# ESP8266ServoGPIOServerAP.net
KiCad netlist of a schematic drawn in EAGLE
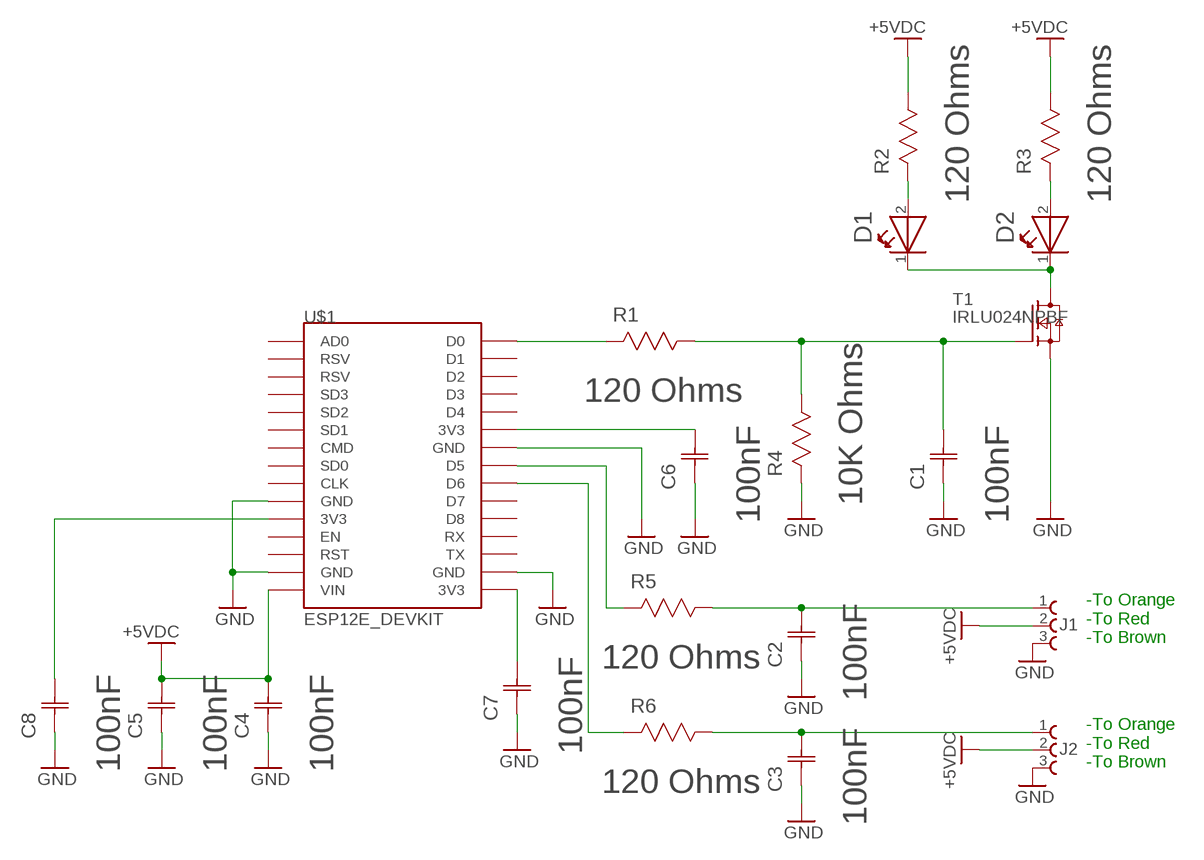
[diagram p0: schematic, sheet 1]

(export (version "E")
  (design (tool "Eeschema 10.0.6"))
  (components
    (comp (ref "C1")
      (value "100nF")
      (footprint "eagle-import:CAPC2013X135N")
      (fields (field (name "MPN") "GRM21BR60J226ME39L ") (field (name "TOLERANCE") "±20%"))
      (libsource (lib "eagle-import") (part "GRM21BR60J226ME39L"))
    )
    (comp (ref "C2")
      (value "100nF")
      (footprint "eagle-import:CAPC2013X135N")
      (fields (field (name "MPN") "GRM21BR60J226ME39L ") (field (name "TOLERANCE") "±20%"))
      (libsource (lib "eagle-import") (part "GRM21BR60J226ME39L"))
    )
    (comp (ref "C3")
      (value "100nF")
      (footprint "eagle-import:CAPC2013X135N")
      (fields (field (name "MPN") "GRM21BR60J226ME39L ") (field (name "TOLERANCE") "±20%"))
      (libsource (lib "eagle-import") (part "GRM21BR60J226ME39L"))
    )
    (comp (ref "C4")
      (value "100nF")
      (footprint "eagle-import:CAPC2013X135N")
      (fields (field (name "MPN") "GRM21BR60J226ME39L ") (field (name "TOLERANCE") "±20%"))
      (libsource (lib "eagle-import") (part "GRM21BR60J226ME39L"))
    )
    (comp (ref "C5")
      (value "100nF")
      (footprint "eagle-import:CAPC2013X135N")
      (fields (field (name "MPN") "GRM21BR60J226ME39L ") (field (name "TOLERANCE") "±20%"))
      (libsource (lib "eagle-import") (part "GRM21BR60J226ME39L"))
    )
    (comp (ref "C6")
      (value "100nF")
      (footprint "eagle-import:CAPC2013X135N")
      (fields (field (name "MPN") "GRM21BR60J226ME39L ") (field (name "TOLERANCE") "±20%"))
      (libsource (lib "eagle-import") (part "GRM21BR60J226ME39L"))
    )
    (comp (ref "C7")
      (value "100nF")
      (footprint "eagle-import:CAPC2013X135N")
      (fields (field (name "MPN") "GRM21BR60J226ME39L ") (field (name "TOLERANCE") "±20%"))
      (libsource (lib "eagle-import") (part "GRM21BR60J226ME39L"))
    )
    (comp (ref "C8")
      (value "100nF")
      (footprint "eagle-import:CAPC2013X135N")
      (fields (field (name "MPN") "GRM21BR60J226ME39L ") (field (name "TOLERANCE") "±20%"))
      (libsource (lib "eagle-import") (part "GRM21BR60J226ME39L"))
    )
    (comp (ref "D1")
      (value "WL-SMTW-150141AS73100-A")
      (footprint "eagle-import:3528-2PIN")
      (fields
        (field (name "MANUFACTURER") "Würth Elektronik eiSos GmbH")
        (field (name "CREATED-BY") "Christin Otto")
      )
      (libsource (lib "eagle-import") (part "WL-SMTW-150141AS73100-A"))
    )
    (comp (ref "D2")
      (value "WL-SMTW-150141AS73100-A")
      (footprint "eagle-import:3528-2PIN")
      (fields
        (field (name "MANUFACTURER") "Würth Elektronik eiSos GmbH")
        (field (name "CREATED-BY") "Christin Otto")
      )
      (libsource (lib "eagle-import") (part "WL-SMTW-150141AS73100-A"))
    )
    (comp (ref "J1")
      (value "61300311121")
      (footprint "eagle-import:61300311121")
      (libsource (lib "eagle-import") (part "61300311121"))
    )
    (comp (ref "J2")
      (value "61300311121")
      (footprint "eagle-import:61300311121")
      (libsource (lib "eagle-import") (part "61300311121"))
    )
    (comp (ref "R1")
      (value "120 Ohms")
      (footprint "eagle-import:RESC3216X71N")
      (fields (field (name "MPN") "LR1206-R05FI") (field (name "TOLERANCE") "±1%"))
      (libsource (lib "eagle-import") (part "LR1206-R05FI"))
    )
    (comp (ref "R2")
      (value "120 Ohms")
      (footprint "eagle-import:RESC3216X71N")
      (fields (field (name "MPN") "LR1206-R05FI") (field (name "TOLERANCE") "±1%"))
      (libsource (lib "eagle-import") (part "LR1206-R05FI"))
    )
    (comp (ref "R3")
      (value "120 Ohms")
      (footprint "eagle-import:RESC3216X71N")
      (fields (field (name "MPN") "LR1206-R05FI") (field (name "TOLERANCE") "±1%"))
      (libsource (lib "eagle-import") (part "LR1206-R05FI"))
    )
    (comp (ref "R4")
      (value "10K Ohms")
      (footprint "eagle-import:RESC3216X71N")
      (fields (field (name "MPN") "LR1206-R05FI") (field (name "TOLERANCE") "±1%"))
      (libsource (lib "eagle-import") (part "LR1206-R05FI"))
    )
    (comp (ref "R5")
      (value "120 Ohms")
      (footprint "eagle-import:RESC3216X71N")
      (fields (field (name "MPN") "LR1206-R05FI") (field (name "TOLERANCE") "±1%"))
      (libsource (lib "eagle-import") (part "LR1206-R05FI"))
    )
    (comp (ref "R6")
      (value "120 Ohms")
      (footprint "eagle-import:RESC3216X71N")
      (fields (field (name "MPN") "LR1206-R05FI") (field (name "TOLERANCE") "±1%"))
      (libsource (lib "eagle-import") (part "LR1206-R05FI"))
    )
    (comp (ref "T1")
      (value "IRLU024NPBF")
      (footprint "eagle-import:SOT23")
      (libsource (lib "eagle-import") (part "2N7002E"))
    )
    (comp (ref "U$1")
      (value "ESP12E_DEVKIT")
      (footprint "eagle-import:ESP12E_DEVKIT")
      (libsource (lib "eagle-import") (part "ESP12E_DEVKIT"))
    )
  )
  (nets
    (net (code "1") (name "+5VDC") (class "Default")
      (node (ref "C1") (pin "1") (pinfunction "C1_1") (pintype "passive"))
      (node (ref "C2") (pin "1") (pinfunction "C1_1") (pintype "passive"))
      (node (ref "C3") (pin "1") (pinfunction "C1_1") (pintype "passive"))
      (node (ref "C4") (pin "1") (pinfunction "C1_1") (pintype "passive"))
      (node (ref "C4") (pin "2") (pinfunction "C2_2") (pintype "passive"))
      (node (ref "C5") (pin "1") (pinfunction "C1_1") (pintype "passive"))
      (node (ref "C5") (pin "2") (pinfunction "C2_2") (pintype "passive"))
      (node (ref "C6") (pin "1") (pinfunction "C1_1") (pintype "passive"))
      (node (ref "C7") (pin "1") (pinfunction "C1_1") (pintype "passive"))
      (node (ref "C8") (pin "1") (pinfunction "C1_1") (pintype "passive"))
      (node (ref "J1") (pin "2") (pinfunction "2_2") (pintype "passive"))
      (node (ref "J1") (pin "3") (pinfunction "3_3") (pintype "passive"))
      (node (ref "J2") (pin "2") (pinfunction "2_2") (pintype "passive"))
      (node (ref "J2") (pin "3") (pinfunction "3_3") (pintype "passive"))
      (node (ref "R2") (pin "1") (pinfunction "R1_1") (pintype "passive"))
      (node (ref "R3") (pin "1") (pinfunction "R1_1") (pintype "passive"))
      (node (ref "R4") (pin "2") (pinfunction "R2_2") (pintype "passive"))
      (node (ref "T1") (pin "2") (pinfunction "S_2") (pintype "passive"))
      (node (ref "U$1") (pin "GND@0") (pinfunction "GND_GND@0") (pintype "bidirectional"))
      (node (ref "U$1") (pin "GND@1") (pinfunction "GND_GND@1") (pintype "bidirectional"))
      (node (ref "U$1") (pin "GND@2") (pinfunction "GND_GND@2") (pintype "bidirectional"))
      (node (ref "U$1") (pin "GND@3") (pinfunction "GND_GND@3") (pintype "bidirectional"))
      (node (ref "U$1") (pin "VIN") (pinfunction "VIN_VIN") (pintype "bidirectional"))
    )
    (net (code "2") (name "Net-(C1-C2)") (class "Default")
      (node (ref "C1") (pin "2") (pinfunction "C2_2") (pintype "passive"))
      (node (ref "R1") (pin "1") (pinfunction "R1_1") (pintype "passive"))
      (node (ref "R4") (pin "1") (pinfunction "R1_1") (pintype "passive"))
      (node (ref "T1") (pin "1") (pinfunction "G_1") (pintype "passive"))
    )
    (net (code "3") (name "Net-(C2-C2)") (class "Default")
      (node (ref "C2") (pin "2") (pinfunction "C2_2") (pintype "passive"))
      (node (ref "J1") (pin "1") (pinfunction "1_1") (pintype "passive"))
      (node (ref "R5") (pin "1") (pinfunction "R1_1") (pintype "passive"))
    )
    (net (code "4") (name "Net-(C3-C2)") (class "Default")
      (node (ref "C3") (pin "2") (pinfunction "C2_2") (pintype "passive"))
      (node (ref "J2") (pin "1") (pinfunction "1_1") (pintype "passive"))
      (node (ref "R6") (pin "1") (pinfunction "R1_1") (pintype "passive"))
    )
    (net (code "5") (name "Net-(C6-C2)") (class "Default")
      (node (ref "C6") (pin "2") (pinfunction "C2_2") (pintype "passive"))
      (node (ref "U$1") (pin "3V3@1") (pinfunction "3V3_3V3@1") (pintype "bidirectional"))
    )
    (net (code "6") (name "Net-(C7-C2)") (class "Default")
      (node (ref "C7") (pin "2") (pinfunction "C2_2") (pintype "passive"))
      (node (ref "U$1") (pin "3V3@2") (pinfunction "3V3_3V3@2") (pintype "bidirectional"))
    )
    (net (code "7") (name "Net-(C8-C2)") (class "Default")
      (node (ref "C8") (pin "2") (pinfunction "C2_2") (pintype "passive"))
      (node (ref "U$1") (pin "3V3@0") (pinfunction "3V3_3V3@0") (pintype "bidirectional"))
    )
    (net (code "8") (name "Net-(D1-A)") (class "Default")
      (node (ref "D1") (pin "2") (pinfunction "A_2") (pintype "bidirectional"))
      (node (ref "R2") (pin "2") (pinfunction "R2_2") (pintype "passive"))
    )
    (net (code "9") (name "Net-(D1-K)") (class "Default")
      (node (ref "D1") (pin "1") (pinfunction "K_1") (pintype "bidirectional"))
      (node (ref "D2") (pin "1") (pinfunction "K_1") (pintype "bidirectional"))
      (node (ref "T1") (pin "3") (pinfunction "D_3") (pintype "passive"))
    )
    (net (code "10") (name "Net-(D2-A)") (class "Default")
      (node (ref "D2") (pin "2") (pinfunction "A_2") (pintype "bidirectional"))
      (node (ref "R3") (pin "2") (pinfunction "R2_2") (pintype "passive"))
    )
    (net (code "11") (name "Net-(R1-R2)") (class "Default")
      (node (ref "R1") (pin "2") (pinfunction "R2_2") (pintype "passive"))
      (node (ref "U$1") (pin "D0") (pinfunction "D0_D0") (pintype "bidirectional"))
    )
    (net (code "12") (name "Net-(R5-R2)") (class "Default")
      (node (ref "R5") (pin "2") (pinfunction "R2_2") (pintype "passive"))
      (node (ref "U$1") (pin "D5") (pinfunction "D5_D5") (pintype "bidirectional"))
    )
    (net (code "13") (name "Net-(R6-R2)") (class "Default")
      (node (ref "R6") (pin "2") (pinfunction "R2_2") (pintype "passive"))
      (node (ref "U$1") (pin "D6") (pinfunction "D6_D6") (pintype "bidirectional"))
    )
    (net (code "14") (name "unconnected-(U$1-PadAD0)") (class "Default")
      (node (ref "U$1") (pin "AD0") (pinfunction "AD0_AD0") (pintype "bidirectional"))
    )
    (net (code "15") (name "unconnected-(U$1-PadCLK)") (class "Default")
      (node (ref "U$1") (pin "CLK") (pinfunction "CLK_CLK") (pintype "bidirectional"))
    )
    (net (code "16") (name "unconnected-(U$1-PadCMD)") (class "Default")
      (node (ref "U$1") (pin "CMD") (pinfunction "CMD_CMD") (pintype "bidirectional"))
    )
    (net (code "17") (name "unconnected-(U$1-PadD1)") (class "Default")
      (node (ref "U$1") (pin "D1") (pinfunction "D1_D1") (pintype "bidirectional"))
    )
    (net (code "18") (name "unconnected-(U$1-PadD2)") (class "Default")
      (node (ref "U$1") (pin "D2") (pinfunction "D2_D2") (pintype "bidirectional"))
    )
    (net (code "19") (name "unconnected-(U$1-PadD3)") (class "Default")
      (node (ref "U$1") (pin "D3") (pinfunction "D3_D3") (pintype "bidirectional"))
    )
    (net (code "20") (name "unconnected-(U$1-PadD4)") (class "Default")
      (node (ref "U$1") (pin "D4") (pinfunction "D4_D4") (pintype "bidirectional"))
    )
    (net (code "21") (name "unconnected-(U$1-PadD7)") (class "Default")
      (node (ref "U$1") (pin "D7") (pinfunction "D7_D7") (pintype "bidirectional"))
    )
    (net (code "22") (name "unconnected-(U$1-PadD8)") (class "Default")
      (node (ref "U$1") (pin "D8") (pinfunction "D8_D8") (pintype "bidirectional"))
    )
    (net (code "23") (name "unconnected-(U$1-PadEN)") (class "Default")
      (node (ref "U$1") (pin "EN") (pinfunction "EN_EN") (pintype "bidirectional"))
    )
    (net (code "24") (name "unconnected-(U$1-PadRST)") (class "Default")
      (node (ref "U$1") (pin "RST") (pinfunction "RST_RST") (pintype "bidirectional"))
    )
    (net (code "25") (name "unconnected-(U$1-PadRX)") (class "Default")
      (node (ref "U$1") (pin "RX") (pinfunction "RX_RX") (pintype "bidirectional"))
    )
    (net (code "26") (name "unconnected-(U$1-PadSD0)") (class "Default")
      (node (ref "U$1") (pin "SD0") (pinfunction "SD0_SD0") (pintype "bidirectional"))
    )
    (net (code "27") (name "unconnected-(U$1-PadSD1)") (class "Default")
      (node (ref "U$1") (pin "SD1") (pinfunction "SD1_SD1") (pintype "bidirectional"))
    )
    (net (code "28") (name "unconnected-(U$1-PadSD2)") (class "Default")
      (node (ref "U$1") (pin "SD2") (pinfunction "SD2_SD2") (pintype "bidirectional"))
    )
    (net (code "29") (name "unconnected-(U$1-PadSD3)") (class "Default")
      (node (ref "U$1") (pin "SD3") (pinfunction "SD3_SD3") (pintype "bidirectional"))
    )
    (net (code "30") (name "unconnected-(U$1-PadTX)") (class "Default")
      (node (ref "U$1") (pin "TX") (pinfunction "TX_TX") (pintype "bidirectional"))
    )
    (net (code "31") (name "unconnected-(U$1-RSV-PadRSV@0)") (class "Default")
      (node (ref "U$1") (pin "RSV@0") (pinfunction "RSV_RSV@0") (pintype "bidirectional"))
    )
    (net (code "32") (name "unconnected-(U$1-RSV-PadRSV@1)") (class "Default")
      (node (ref "U$1") (pin "RSV@1") (pinfunction "RSV_RSV@1") (pintype "bidirectional"))
    )
  )
)
